# bitbox_rev2b_05_sym.net
KiCad netlist of a schematic drawn in EAGLE
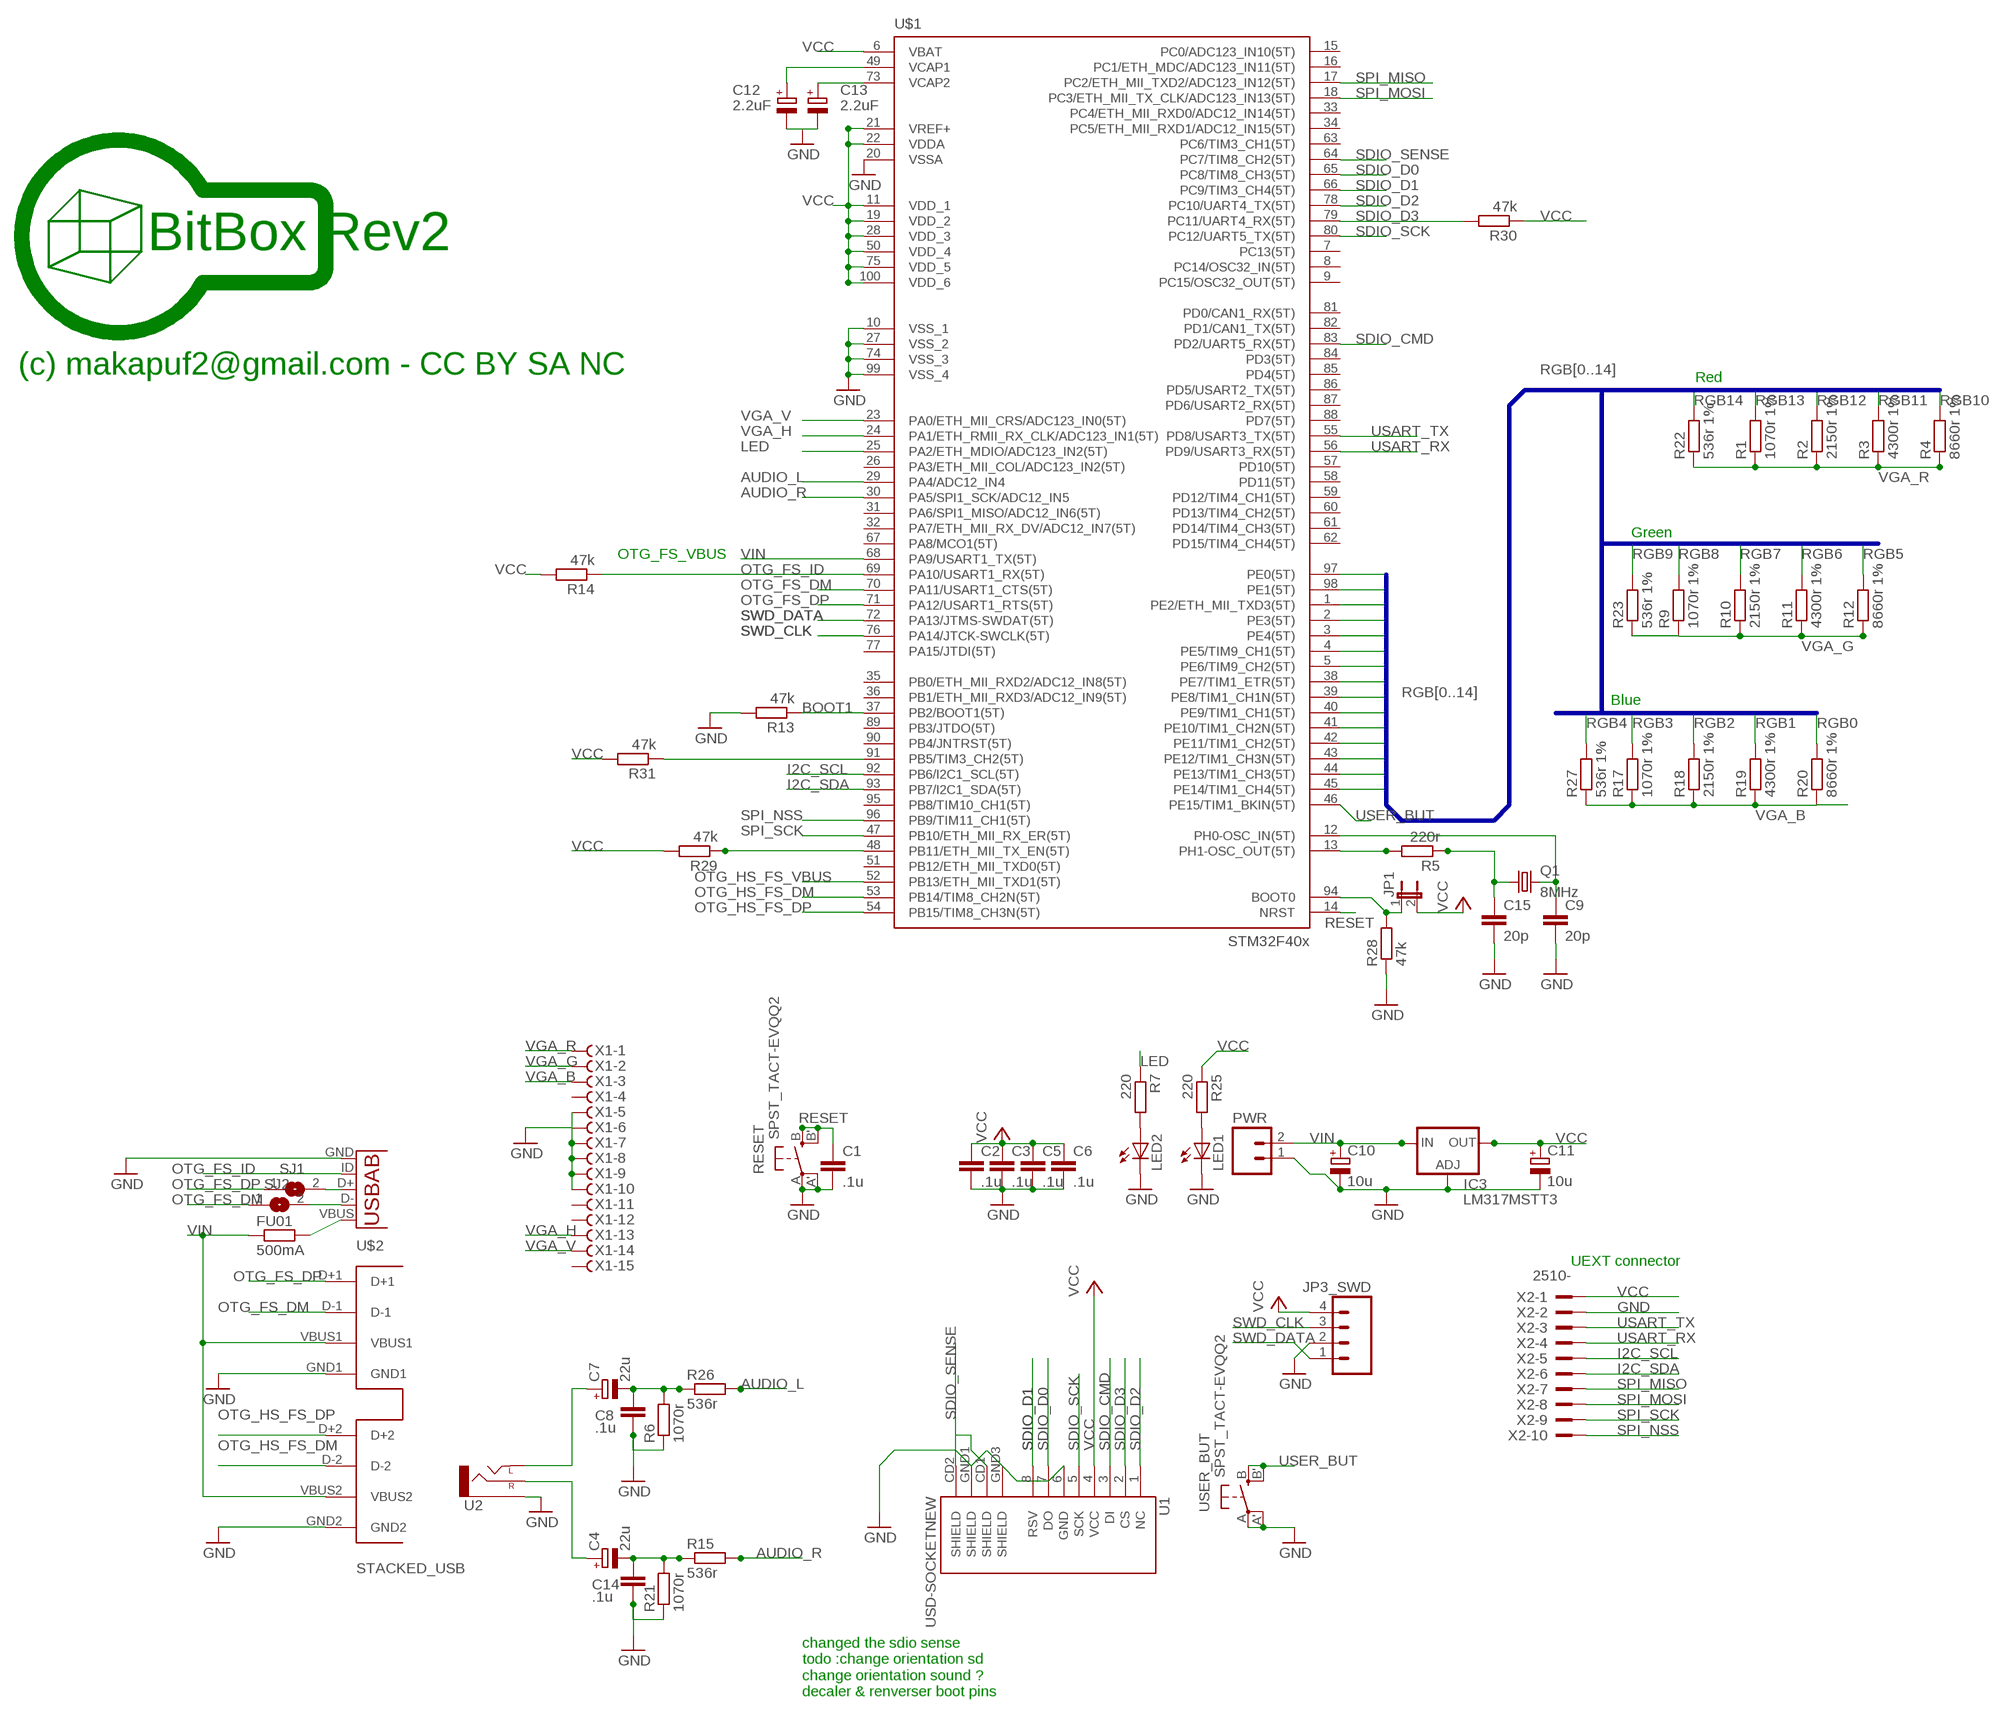
[diagram p0: schematic, sheet 1]

(export (version "E")
  (design (tool "Eeschema 10.0.6"))
  (components
    (comp (ref "C1")
      (value ".1u")
      (footprint "eagle-import:C0603")
      (libsource (lib "eagle-import") (part "C-EUC0603"))
    )
    (comp (ref "C2")
      (value ".1u")
      (footprint "eagle-import:C0603")
      (libsource (lib "eagle-import") (part "C-EUC0603"))
    )
    (comp (ref "C3")
      (value ".1u")
      (footprint "eagle-import:C0603")
      (libsource (lib "eagle-import") (part "C-EUC0603"))
    )
    (comp (ref "C4")
      (value "22u")
      (footprint "eagle-import:153CLV-0505")
      (libsource (lib "eagle-import") (part "CPOL-EU153CLV-0505"))
    )
    (comp (ref "C5")
      (value ".1u")
      (footprint "eagle-import:C0603")
      (libsource (lib "eagle-import") (part "C-EUC0603"))
    )
    (comp (ref "C6")
      (value ".1u")
      (footprint "eagle-import:C0603")
      (libsource (lib "eagle-import") (part "C-EUC0603"))
    )
    (comp (ref "C7")
      (value "22u")
      (footprint "eagle-import:153CLV-0505")
      (libsource (lib "eagle-import") (part "CPOL-EU153CLV-0505"))
    )
    (comp (ref "C8")
      (value ".1u")
      (footprint "eagle-import:C0603")
      (libsource (lib "eagle-import") (part "C-EUC0603"))
    )
    (comp (ref "C9")
      (value "20p")
      (footprint "eagle-import:C0603")
      (libsource (lib "eagle-import") (part "C-EUC0603"))
    )
    (comp (ref "C10")
      (value "10u")
      (footprint "eagle-import:SMC_A")
      (libsource (lib "eagle-import") (part "CPOL-EUSMCA"))
    )
    (comp (ref "C11")
      (value "10u")
      (footprint "eagle-import:SMC_A")
      (libsource (lib "eagle-import") (part "CPOL-EUSMCA"))
    )
    (comp (ref "C12")
      (value "2.2uF")
      (footprint "eagle-import:SMC_A")
      (libsource (lib "eagle-import") (part "CPOL-EUSMCA"))
    )
    (comp (ref "C13")
      (value "2.2uF")
      (footprint "eagle-import:SMC_A")
      (libsource (lib "eagle-import") (part "CPOL-EUSMCA"))
    )
    (comp (ref "C14")
      (value ".1u")
      (footprint "eagle-import:C0603")
      (libsource (lib "eagle-import") (part "C-EUC0603"))
    )
    (comp (ref "C15")
      (value "20p")
      (footprint "eagle-import:C0603")
      (libsource (lib "eagle-import") (part "C-EUC0603"))
    )
    (comp (ref "FU01")
      (value "500mA")
      (footprint "eagle-import:R1206")
      (libsource (lib "eagle-import") (part "R-EU_R1206"))
    )
    (comp (ref "IC3")
      (value "LM317MSTT3")
      (footprint "eagle-import:SOT223")
      (libsource (lib "eagle-import") (part "LM317?MSTT3"))
    )
    (comp (ref "JP1")
      (value "JP1E")
      (footprint "eagle-import:JP1")
      (libsource (lib "eagle-import") (part "JP1E"))
    )
    (comp (ref "JP3_SWD")
      (value "M04PTH")
      (footprint "eagle-import:1X04")
      (libsource (lib "eagle-import") (part "M04PTH"))
    )
    (comp (ref "LED1")
      (value "LEDCHIPLED_0805")
      (footprint "eagle-import:CHIPLED_0805")
      (libsource (lib "eagle-import") (part "LEDCHIPLED_0805"))
    )
    (comp (ref "LED2")
      (value "LEDCHIPLED_0805")
      (footprint "eagle-import:CHIPLED_0805")
      (libsource (lib "eagle-import") (part "LEDCHIPLED_0805"))
    )
    (comp (ref "PWR")
      (value "M02PTH")
      (footprint "eagle-import:1X02")
      (libsource (lib "eagle-import") (part "M02PTH"))
    )
    (comp (ref "Q1")
      (value "8MHz")
      (footprint "eagle-import:SM49")
      (fields (field (name "OC_FARNELL") "unknown"))
      (libsource (lib "eagle-import") (part "CRYSTALSM49"))
    )
    (comp (ref "R1")
      (value "1070r 1%")
      (footprint "eagle-import:R0603")
      (libsource (lib "eagle-import") (part "R-EU_R0603"))
    )
    (comp (ref "R2")
      (value "2150r 1%")
      (footprint "eagle-import:R0603")
      (libsource (lib "eagle-import") (part "R-EU_R0603"))
    )
    (comp (ref "R3")
      (value "4300r 1%")
      (footprint "eagle-import:R0603")
      (libsource (lib "eagle-import") (part "R-EU_R0603"))
    )
    (comp (ref "R4")
      (value "8660r 1%")
      (footprint "eagle-import:R0603")
      (libsource (lib "eagle-import") (part "R-EU_R0603"))
    )
    (comp (ref "R5")
      (value "220r")
      (footprint "eagle-import:R0603")
      (libsource (lib "eagle-import") (part "R-EU_R0603"))
    )
    (comp (ref "R6")
      (value "1070r")
      (footprint "eagle-import:R0603")
      (libsource (lib "eagle-import") (part "R-EU_R0603"))
    )
    (comp (ref "R7")
      (value "220")
      (footprint "eagle-import:R0603")
      (libsource (lib "eagle-import") (part "R-EU_R0603"))
    )
    (comp (ref "R9")
      (value "1070r 1%")
      (footprint "eagle-import:R0603")
      (libsource (lib "eagle-import") (part "R-EU_R0603"))
    )
    (comp (ref "R10")
      (value "2150r 1%")
      (footprint "eagle-import:R0603")
      (libsource (lib "eagle-import") (part "R-EU_R0603"))
    )
    (comp (ref "R11")
      (value "4300r 1%")
      (footprint "eagle-import:R0603")
      (libsource (lib "eagle-import") (part "R-EU_R0603"))
    )
    (comp (ref "R12")
      (value "8660r 1%")
      (footprint "eagle-import:R0603")
      (libsource (lib "eagle-import") (part "R-EU_R0603"))
    )
    (comp (ref "R13")
      (value "47k")
      (footprint "eagle-import:R0603")
      (libsource (lib "eagle-import") (part "R-EU_R0603"))
    )
    (comp (ref "R14")
      (value "47k")
      (footprint "eagle-import:R0603")
      (libsource (lib "eagle-import") (part "R-EU_R0603"))
    )
    (comp (ref "R15")
      (value "536r")
      (footprint "eagle-import:R0603")
      (libsource (lib "eagle-import") (part "R-EU_R0603"))
    )
    (comp (ref "R17")
      (value "1070r 1%")
      (footprint "eagle-import:R0603")
      (libsource (lib "eagle-import") (part "R-EU_R0603"))
    )
    (comp (ref "R18")
      (value "2150r 1%")
      (footprint "eagle-import:R0603")
      (libsource (lib "eagle-import") (part "R-EU_R0603"))
    )
    (comp (ref "R19")
      (value "4300r 1%")
      (footprint "eagle-import:R0603")
      (libsource (lib "eagle-import") (part "R-EU_R0603"))
    )
    (comp (ref "R20")
      (value "8660r 1%")
      (footprint "eagle-import:R0603")
      (libsource (lib "eagle-import") (part "R-EU_R0603"))
    )
    (comp (ref "R21")
      (value "1070r")
      (footprint "eagle-import:R0603")
      (libsource (lib "eagle-import") (part "R-EU_R0603"))
    )
    (comp (ref "R22")
      (value "536r 1%")
      (footprint "eagle-import:R0603")
      (libsource (lib "eagle-import") (part "R-EU_R0603"))
    )
    (comp (ref "R23")
      (value "536r 1%")
      (footprint "eagle-import:R0603")
      (libsource (lib "eagle-import") (part "R-EU_R0603"))
    )
    (comp (ref "R25")
      (value "220")
      (footprint "eagle-import:R0603")
      (libsource (lib "eagle-import") (part "R-EU_R0603"))
    )
    (comp (ref "R26")
      (value "536r")
      (footprint "eagle-import:R0603")
      (libsource (lib "eagle-import") (part "R-EU_R0603"))
    )
    (comp (ref "R27")
      (value "536r 1%")
      (footprint "eagle-import:R0603")
      (libsource (lib "eagle-import") (part "R-EU_R0603"))
    )
    (comp (ref "R28")
      (value "47k")
      (footprint "eagle-import:R0603")
      (libsource (lib "eagle-import") (part "R-EU_R0603"))
    )
    (comp (ref "R29")
      (value "47k")
      (footprint "eagle-import:R0603")
      (libsource (lib "eagle-import") (part "R-EU_R0603"))
    )
    (comp (ref "R30")
      (value "47k")
      (footprint "eagle-import:R0603")
      (libsource (lib "eagle-import") (part "R-EU_R0603"))
    )
    (comp (ref "R31")
      (value "47k")
      (footprint "eagle-import:R0603")
      (libsource (lib "eagle-import") (part "R-EU_R0603"))
    )
    (comp (ref "RESET")
      (value "SPST_TACT-EVQQ2")
      (footprint "eagle-import:EVQ-Q2")
      (libsource (lib "eagle-import") (part "SPST_TACT-EVQQ2"))
    )
    (comp (ref "SJ1") (value "SJ") (footprint "eagle-import:SJ") (libsource (lib "eagle-import") (part "SJ")))
    (comp (ref "SJ2") (value "SJ") (footprint "eagle-import:SJ") (libsource (lib "eagle-import") (part "SJ")))
    (comp (ref "U$1")
      (value "STM32F407V")
      (footprint "eagle-import:TQFP100")
      (libsource (lib "eagle-import") (part "STM32F407V"))
    )
    (comp (ref "U$2")
      (value "STACKED_USB")
      (footprint "eagle-import:2STACKED")
      (libsource (lib "eagle-import") (part "STACKED_USB"))
    )
    (comp (ref "U1")
      (value "USD-SOCKETNEW")
      (footprint "eagle-import:MICRO-SD-SOCKET-PP")
      (libsource (lib "eagle-import") (part "USD-SOCKETNEW"))
    )
    (comp (ref "U2")
      (value "AUDIO-JACKPTH")
      (footprint "eagle-import:AUDIO-JACK")
      (libsource (lib "eagle-import") (part "AUDIO-JACKPTH"))
    )
    (comp (ref "U3")
      (value "USB-AB")
      (footprint "eagle-import:USB-AB-MICRO-SMD")
      (libsource (lib "eagle-import") (part "USB-AB"))
    )
    (comp (ref "USER_BUT")
      (value "SPST_TACT-EVQQ2")
      (footprint "eagle-import:EVQ-Q2")
      (libsource (lib "eagle-import") (part "SPST_TACT-EVQQ2"))
    )
    (comp (ref "X1")
      (value "HF15HS")
      (footprint "eagle-import:HDF15H")
      (libsource (lib "eagle-import") (part "HF15?SH"))
    )
    (comp (ref "X2")
      (value "2510-")
      (footprint "eagle-import:PAK100_2500-10")
      (fields (field (name "MF") "3M") (field (name "MPN") "2510-6002UB"))
      (libsource (lib "eagle-import") (part "2510-"))
    )
  )
  (nets
    (net (code "1") (name "/AUDIO_L") (class "Default")
      (node (ref "R26") (pin "2") (pinfunction "2_2") (pintype "passive"))
      (node (ref "U$1") (pin "29") (pinfunction "PA4/ADC12_IN4_29") (pintype "bidirectional"))
    )
    (net (code "2") (name "/AUDIO_R") (class "Default")
      (node (ref "R15") (pin "2") (pinfunction "2_2") (pintype "passive"))
      (node (ref "U$1") (pin "30") (pinfunction "PA5/SPI1_SCK/ADC12_IN5_30") (pintype "bidirectional"))
    )
    (net (code "3") (name "/BOOT1") (class "Default")
      (node (ref "R13") (pin "1") (pinfunction "1_1") (pintype "passive"))
      (node (ref "U$1") (pin "37") (pinfunction "PB2/BOOT1(5T)_37") (pintype "bidirectional"))
    )
    (net (code "4") (name "/I2C_SCL") (class "Default")
      (node (ref "U$1") (pin "92") (pinfunction "PB6/I2C1_SCL(5T)_92") (pintype "bidirectional"))
      (node (ref "X2") (pin "5") (pinfunction "KL_5") (pintype "passive"))
    )
    (net (code "5") (name "/I2C_SDA") (class "Default")
      (node (ref "U$1") (pin "93") (pinfunction "PB7/I2C1_SDA(5T)_93") (pintype "bidirectional"))
      (node (ref "X2") (pin "6") (pinfunction "KL_6") (pintype "passive"))
    )
    (net (code "6") (name "/LED") (class "Default")
      (node (ref "R7") (pin "1") (pinfunction "1_1") (pintype "passive"))
      (node (ref "U$1") (pin "25") (pinfunction "PA2/ETH_MDIO/ADC123_IN2(5T)_25") (pintype "bidirectional"))
    )
    (net (code "7") (name "/OTG_FS_DM") (class "Default")
      (node (ref "SJ2") (pin "1") (pinfunction "1_1") (pintype "passive"))
      (node (ref "U$1") (pin "70") (pinfunction "PA11/USART1_CTS(5T)_70") (pintype "bidirectional"))
      (node (ref "U$2") (pin "D-1") (pinfunction "D-1_D-1") (pintype "bidirectional"))
    )
    (net (code "8") (name "/OTG_FS_DP") (class "Default")
      (node (ref "SJ1") (pin "1") (pinfunction "1_1") (pintype "passive"))
      (node (ref "U$1") (pin "71") (pinfunction "PA12/USART1_RTS(5T)_71") (pintype "bidirectional"))
      (node (ref "U$2") (pin "D+1") (pinfunction "D+1_D+1") (pintype "bidirectional"))
    )
    (net (code "9") (name "/OTG_FS_ID") (class "Default")
      (node (ref "R14") (pin "1") (pinfunction "1_1") (pintype "passive"))
      (node (ref "U$1") (pin "69") (pinfunction "PA10/USART1_RX(5T)_69") (pintype "bidirectional"))
      (node (ref "U3") (pin "ID") (pinfunction "USBID_ID") (pintype "bidirectional"))
    )
    (net (code "10") (name "/OTG_HS_FS_DM") (class "Default")
      (node (ref "U$1") (pin "53") (pinfunction "PB14/TIM8_CH2N(5T)_53") (pintype "bidirectional"))
      (node (ref "U$2") (pin "D-2") (pinfunction "D-2_D-2") (pintype "bidirectional"))
    )
    (net (code "11") (name "/OTG_HS_FS_DP") (class "Default")
      (node (ref "U$1") (pin "54") (pinfunction "PB15/TIM8_CH3N(5T)_54") (pintype "bidirectional"))
      (node (ref "U$2") (pin "D+2") (pinfunction "D+2_D+2") (pintype "bidirectional"))
    )
    (net (code "12") (name "/OTG_HS_FS_VBUS") (class "Default")
      (node (ref "U$1") (pin "52") (pinfunction "PB13/ETH_MII_TXD1(5T)_52") (pintype "bidirectional"))
    )
    (net (code "13") (name "/RESET") (class "Default")
      (node (ref "C1") (pin "1") (pinfunction "1_1") (pintype "passive"))
      (node (ref "RESET") (pin "B") (pinfunction "S_B") (pintype "passive"))
      (node (ref "RESET") (pin "B'") (pinfunction "S1_B'") (pintype "passive"))
      (node (ref "U$1") (pin "14") (pinfunction "NRST_14") (pintype "bidirectional"))
    )
    (net (code "14") (name "/RGB0") (class "Default")
      (node (ref "R20") (pin "2") (pinfunction "2_2") (pintype "passive"))
      (node (ref "U$1") (pin "97") (pinfunction "PE0(5T)_97") (pintype "bidirectional"))
    )
    (net (code "15") (name "/RGB1") (class "Default")
      (node (ref "R19") (pin "2") (pinfunction "2_2") (pintype "passive"))
      (node (ref "U$1") (pin "98") (pinfunction "PE1(5T)_98") (pintype "bidirectional"))
    )
    (net (code "16") (name "/RGB2") (class "Default")
      (node (ref "R18") (pin "2") (pinfunction "2_2") (pintype "passive"))
      (node (ref "U$1") (pin "1") (pinfunction "PE2/ETH_MII_TXD3(5T)_1") (pintype "bidirectional"))
    )
    (net (code "17") (name "/RGB3") (class "Default")
      (node (ref "R17") (pin "2") (pinfunction "2_2") (pintype "passive"))
      (node (ref "U$1") (pin "2") (pinfunction "PE3(5T)_2") (pintype "bidirectional"))
    )
    (net (code "18") (name "/RGB4") (class "Default")
      (node (ref "R27") (pin "2") (pinfunction "2_2") (pintype "passive"))
      (node (ref "U$1") (pin "3") (pinfunction "PE4(5T)_3") (pintype "bidirectional"))
    )
    (net (code "19") (name "/RGB5") (class "Default")
      (node (ref "R12") (pin "2") (pinfunction "2_2") (pintype "passive"))
      (node (ref "U$1") (pin "4") (pinfunction "PE5/TIM9_CH1(5T)_4") (pintype "bidirectional"))
    )
    (net (code "20") (name "/RGB6") (class "Default")
      (node (ref "R11") (pin "2") (pinfunction "2_2") (pintype "passive"))
      (node (ref "U$1") (pin "5") (pinfunction "PE6/TIM9_CH2(5T)_5") (pintype "bidirectional"))
    )
    (net (code "21") (name "/RGB7") (class "Default")
      (node (ref "R10") (pin "2") (pinfunction "2_2") (pintype "passive"))
      (node (ref "U$1") (pin "38") (pinfunction "PE7/TIM1_ETR(5T)_38") (pintype "bidirectional"))
    )
    (net (code "22") (name "/RGB8") (class "Default")
      (node (ref "R9") (pin "2") (pinfunction "2_2") (pintype "passive"))
      (node (ref "U$1") (pin "39") (pinfunction "PE8/TIM1_CH1N(5T)_39") (pintype "bidirectional"))
    )
    (net (code "23") (name "/RGB9") (class "Default")
      (node (ref "R23") (pin "2") (pinfunction "2_2") (pintype "passive"))
      (node (ref "U$1") (pin "40") (pinfunction "PE9/TIM1_CH1(5T)_40") (pintype "bidirectional"))
    )
    (net (code "24") (name "/RGB10") (class "Default")
      (node (ref "R4") (pin "2") (pinfunction "2_2") (pintype "passive"))
      (node (ref "U$1") (pin "41") (pinfunction "PE10/TIM1_CH2N(5T)_41") (pintype "bidirectional"))
    )
    (net (code "25") (name "/RGB11") (class "Default")
      (node (ref "R3") (pin "2") (pinfunction "2_2") (pintype "passive"))
      (node (ref "U$1") (pin "42") (pinfunction "PE11/TIM1_CH2(5T)_42") (pintype "bidirectional"))
    )
    (net (code "26") (name "/RGB12") (class "Default")
      (node (ref "R2") (pin "2") (pinfunction "2_2") (pintype "passive"))
      (node (ref "U$1") (pin "43") (pinfunction "PE12/TIM1_CH3N(5T)_43") (pintype "bidirectional"))
    )
    (net (code "27") (name "/RGB13") (class "Default")
      (node (ref "R1") (pin "2") (pinfunction "2_2") (pintype "passive"))
      (node (ref "U$1") (pin "44") (pinfunction "PE13/TIM1_CH3(5T)_44") (pintype "bidirectional"))
    )
    (net (code "28") (name "/RGB14") (class "Default")
      (node (ref "R22") (pin "2") (pinfunction "2_2") (pintype "passive"))
      (node (ref "U$1") (pin "45") (pinfunction "PE14/TIM1_CH4(5T)_45") (pintype "bidirectional"))
    )
    (net (code "30") (name "/SDIO_CMD") (class "Default")
      (node (ref "U$1") (pin "83") (pinfunction "PD2/UART5_RX(5T)_83") (pintype "bidirectional"))
      (node (ref "U1") (pin "3") (pinfunction "DI_3") (pintype "bidirectional"))
    )
    (net (code "31") (name "/SDIO_D0") (class "Default")
      (node (ref "U$1") (pin "65") (pinfunction "PC8/TIM8_CH3(5T)_65") (pintype "bidirectional"))
      (node (ref "U1") (pin "7") (pinfunction "DO_7") (pintype "bidirectional"))
    )
    (net (code "32") (name "/SDIO_D1") (class "Default")
      (node (ref "U$1") (pin "66") (pinfunction "PC9/TIM3_CH4(5T)_66") (pintype "bidirectional"))
      (node (ref "U1") (pin "8") (pinfunction "RSV_8") (pintype "bidirectional"))
    )
    (net (code "33") (name "/SDIO_D2") (class "Default")
      (node (ref "U$1") (pin "78") (pinfunction "PC10/UART4_TX(5T)_78") (pintype "bidirectional"))
      (node (ref "U1") (pin "1") (pinfunction "NC_1") (pintype "bidirectional"))
    )
    (net (code "34") (name "/SDIO_D3") (class "Default")
      (node (ref "R30") (pin "2") (pinfunction "2_2") (pintype "passive"))
      (node (ref "U$1") (pin "79") (pinfunction "PC11/UART4_RX(5T)_79") (pintype "bidirectional"))
      (node (ref "U1") (pin "2") (pinfunction "CS_2") (pintype "bidirectional"))
    )
    (net (code "35") (name "/SDIO_SCK") (class "Default")
      (node (ref "U$1") (pin "80") (pinfunction "PC12/UART5_TX(5T)_80") (pintype "bidirectional"))
      (node (ref "U1") (pin "5") (pinfunction "SCK_5") (pintype "bidirectional"))
    )
    (net (code "36") (name "/SDIO_SENSE") (class "Default")
      (node (ref "U$1") (pin "64") (pinfunction "PC7/TIM8_CH2(5T)_64") (pintype "bidirectional"))
      (node (ref "U1") (pin "CD1") (pinfunction "SHIELD_CD1") (pintype "bidirectional"))
      (node (ref "U1") (pin "CD2") (pinfunction "SHIELD_CD2") (pintype "bidirectional"))
    )
    (net (code "37") (name "/SPI_MISO") (class "Default")
      (node (ref "U$1") (pin "17") (pinfunction "PC2/ETH_MII_TXD2/ADC123_IN12(5T)_17") (pintype "bidirectional"))
      (node (ref "X2") (pin "7") (pinfunction "KL_7") (pintype "passive"))
    )
    (net (code "38") (name "/SPI_MOSI") (class "Default")
      (node (ref "U$1") (pin "18") (pinfunction "PC3/ETH_MII_TX_CLK/ADC123_IN13(5T)_18") (pintype "bidirectional"))
      (node (ref "X2") (pin "8") (pinfunction "KL_8") (pintype "passive"))
    )
    (net (code "39") (name "/SPI_NSS") (class "Default")
      (node (ref "U$1") (pin "96") (pinfunction "PB9/TIM11_CH1(5T)_96") (pintype "bidirectional"))
      (node (ref "X2") (pin "10") (pinfunction "KL_10") (pintype "passive"))
    )
    (net (code "40") (name "/SPI_SCK") (class "Default")
      (node (ref "U$1") (pin "47") (pinfunction "PB10/ETH_MII_RX_ER(5T)_47") (pintype "bidirectional"))
      (node (ref "X2") (pin "9") (pinfunction "KL_9") (pintype "passive"))
    )
    (net (code "41") (name "/SWD_CLK") (class "Default")
      (node (ref "JP3_SWD") (pin "3") (pinfunction "3_3") (pintype "passive"))
      (node (ref "U$1") (pin "76") (pinfunction "PA14/JTCK-SWCLK(5T)_76") (pintype "bidirectional"))
    )
    (net (code "42") (name "/SWD_DATA") (class "Default")
      (node (ref "JP3_SWD") (pin "1") (pinfunction "1_1") (pintype "passive"))
      (node (ref "U$1") (pin "72") (pinfunction "PA13/JTMS-SWDAT(5T)_72") (pintype "bidirectional"))
    )
    (net (code "43") (name "/USART_RX") (class "Default")
      (node (ref "U$1") (pin "56") (pinfunction "PD9/USART3_RX(5T)_56") (pintype "bidirectional"))
      (node (ref "X2") (pin "4") (pinfunction "KL_4") (pintype "passive"))
    )
    (net (code "44") (name "/USART_TX") (class "Default")
      (node (ref "U$1") (pin "55") (pinfunction "PD8/USART3_TX(5T)_55") (pintype "bidirectional"))
      (node (ref "X2") (pin "3") (pinfunction "KL_3") (pintype "passive"))
    )
    (net (code "45") (name "/USER_BUT") (class "Default")
      (node (ref "U$1") (pin "46") (pinfunction "PE15/TIM1_BKIN(5T)_46") (pintype "bidirectional"))
      (node (ref "USER_BUT") (pin "B") (pinfunction "S_B") (pintype "passive"))
      (node (ref "USER_BUT") (pin "B'") (pinfunction "S1_B'") (pintype "passive"))
    )
    (net (code "46") (name "/VGA_B") (class "Default")
      (node (ref "R17") (pin "1") (pinfunction "1_1") (pintype "passive"))
      (node (ref "R18") (pin "1") (pinfunction "1_1") (pintype "passive"))
      (node (ref "R19") (pin "1") (pinfunction "1_1") (pintype "passive"))
      (node (ref "R20") (pin "1") (pinfunction "1_1") (pintype "passive"))
      (node (ref "R27") (pin "1") (pinfunction "1_1") (pintype "passive"))
      (node (ref "X1") (pin "3") (pinfunction "F_3") (pintype "passive"))
    )
    (net (code "47") (name "/VGA_G") (class "Default")
      (node (ref "R10") (pin "1") (pinfunction "1_1") (pintype "passive"))
      (node (ref "R11") (pin "1") (pinfunction "1_1") (pintype "passive"))
      (node (ref "R12") (pin "1") (pinfunction "1_1") (pintype "passive"))
      (node (ref "R23") (pin "1") (pinfunction "1_1") (pintype "passive"))
      (node (ref "R9") (pin "1") (pinfunction "1_1") (pintype "passive"))
      (node (ref "X1") (pin "2") (pinfunction "F_2") (pintype "passive"))
    )
    (net (code "48") (name "/VGA_H") (class "Default")
      (node (ref "U$1") (pin "24") (pinfunction "PA1/ETH_RMII_RX_CLK/ADC123_IN1(5T)_24") (pintype "bidirectional"))
      (node (ref "X1") (pin "13") (pinfunction "F_13") (pintype "passive"))
    )
    (net (code "49") (name "/VGA_R") (class "Default")
      (node (ref "R1") (pin "1") (pinfunction "1_1") (pintype "passive"))
      (node (ref "R2") (pin "1") (pinfunction "1_1") (pintype "passive"))
      (node (ref "R22") (pin "1") (pinfunction "1_1") (pintype "passive"))
      (node (ref "R3") (pin "1") (pinfunction "1_1") (pintype "passive"))
      (node (ref "R4") (pin "1") (pinfunction "1_1") (pintype "passive"))
      (node (ref "X1") (pin "1") (pinfunction "F_1") (pintype "passive"))
    )
    (net (code "50") (name "/VGA_V") (class "Default")
      (node (ref "U$1") (pin "23") (pinfunction "PA0/ETH_MII_CRS/ADC123_IN0(5T)_23") (pintype "bidirectional"))
      (node (ref "X1") (pin "14") (pinfunction "F_14") (pintype "passive"))
    )
    (net (code "51") (name "/VIN") (class "Default")
      (node (ref "C10") (pin "+") (pinfunction "+_+") (pintype "passive"))
      (node (ref "FU01") (pin "1") (pinfunction "1_1") (pintype "passive"))
      (node (ref "IC3") (pin "3") (pinfunction "IN_3") (pintype "input"))
      (node (ref "PWR") (pin "2") (pinfunction "2_2") (pintype "passive"))
      (node (ref "U$1") (pin "68") (pinfunction "PA9/USART1_TX(5T)_68") (pintype "bidirectional"))
      (node (ref "U$2") (pin "VBUS1") (pinfunction "VBUS1_VBUS1") (pintype "bidirectional"))
      (node (ref "U$2") (pin "VBUS2") (pinfunction "VBUS2_VBUS2") (pintype "bidirectional"))
    )
    (net (code "52") (name "GND") (class "Default")
      (node (ref "C1") (pin "2") (pinfunction "2_2") (pintype "passive"))
      (node (ref "C10") (pin "-") (pinfunction "-_-") (pintype "passive"))
      (node (ref "C11") (pin "-") (pinfunction "-_-") (pintype "passive"))
      (node (ref "C12") (pin "-") (pinfunction "-_-") (pintype "passive"))
      (node (ref "C13") (pin "-") (pinfunction "-_-") (pintype "passive"))
      (node (ref "C14") (pin "2") (pinfunction "2_2") (pintype "passive"))
      (node (ref "C15") (pin "2") (pinfunction "2_2") (pintype "passive"))
      (node (ref "C2") (pin "2") (pinfunction "2_2") (pintype "passive"))
      (node (ref "C3") (pin "2") (pinfunction "2_2") (pintype "passive"))
      (node (ref "C5") (pin "2") (pinfunction "2_2") (pintype "passive"))
      (node (ref "C6") (pin "2") (pinfunction "2_2") (pintype "passive"))
      (node (ref "C8") (pin "2") (pinfunction "2_2") (pintype "passive"))
      (node (ref "C9") (pin "2") (pinfunction "2_2") (pintype "passive"))
      (node (ref "IC3") (pin "1") (pinfunction "ADJ_1") (pintype "input"))
      (node (ref "JP3_SWD") (pin "2") (pinfunction "2_2") (pintype "passive"))
      (node (ref "LED1") (pin "C") (pinfunction "C_C") (pintype "passive"))
      (node (ref "LED2") (pin "C") (pinfunction "C_C") (pintype "passive"))
      (node (ref "PWR") (pin "1") (pinfunction "1_1") (pintype "passive"))
      (node (ref "R13") (pin "2") (pinfunction "2_2") (pintype "passive"))
      (node (ref "R21") (pin "1") (pinfunction "1_1") (pintype "passive"))
      (node (ref "R28") (pin "1") (pinfunction "1_1") (pintype "passive"))
      (node (ref "R6") (pin "1") (pinfunction "1_1") (pintype "passive"))
      (node (ref "RESET") (pin "A") (pinfunction "P_A") (pintype "passive"))
      (node (ref "RESET") (pin "A'") (pinfunction "P1_A'") (pintype "passive"))
      (node (ref "U$1") (pin "10") (pinfunction "VSS_1_10") (pintype "bidirectional"))
      (node (ref "U$1") (pin "20") (pinfunction "VSSA_20") (pintype "bidirectional"))
      (node (ref "U$1") (pin "27") (pinfunction "VSS_2_27") (pintype "bidirectional"))
      (node (ref "U$1") (pin "74") (pinfunction "VSS_3_74") (pintype "bidirectional"))
      (node (ref "U$1") (pin "99") (pinfunction "VSS_4_99") (pintype "bidirectional"))
      (node (ref "U$2") (pin "GND1") (pinfunction "GND1_GND1") (pintype "bidirectional"))
      (node (ref "U$2") (pin "GND2") (pinfunction "GND2_GND2") (pintype "bidirectional"))
      (node (ref "U1") (pin "6") (pinfunction "GND_6") (pintype "bidirectional"))
      (node (ref "U1") (pin "GND1") (pinfunction "SHIELD_GND1") (pintype "bidirectional"))
      (node (ref "U1") (pin "GND3") (pinfunction "SHIELD_GND3") (pintype "bidirectional"))
      (node (ref "U2") (pin "SLEEVE") (pinfunction "SLEEVE_SLEEVE") (pintype "bidirectional"))
      (node (ref "U3") (pin "GND") (pinfunction "GND_GND") (pintype "bidirectional"))
      (node (ref "USER_BUT") (pin "A") (pinfunction "P_A") (pintype "passive"))
      (node (ref "USER_BUT") (pin "A'") (pinfunction "P1_A'") (pintype "passive"))
      (node (ref "X1") (pin "10") (pinfunction "F_10") (pintype "passive"))
      (node (ref "X1") (pin "5") (pinfunction "F_5") (pintype "passive"))
      (node (ref "X1") (pin "6") (pinfunction "F_6") (pintype "passive"))
      (node (ref "X1") (pin "7") (pinfunction "F_7") (pintype "passive"))
      (node (ref "X1") (pin "8") (pinfunction "F_8") (pintype "passive"))
      (node (ref "X1") (pin "9") (pinfunction "F_9") (pintype "passive"))
      (node (ref "X2") (pin "2") (pinfunction "KL_2") (pintype "passive"))
    )
    (net (code "53") (name "Net-(C7-Pad-)") (class "Default")
      (node (ref "C7") (pin "-") (pinfunction "-_-") (pintype "passive"))
      (node (ref "C8") (pin "1") (pinfunction "1_1") (pintype "passive"))
      (node (ref "R26") (pin "1") (pinfunction "1_1") (pintype "passive"))
      (node (ref "R6") (pin "2") (pinfunction "2_2") (pintype "passive"))
    )
    (net (code "54") (name "Net-(C14-Pad1)") (class "Default")
      (node (ref "C14") (pin "1") (pinfunction "1_1") (pintype "passive"))
      (node (ref "C4") (pin "-") (pinfunction "-_-") (pintype "passive"))
      (node (ref "R15") (pin "1") (pinfunction "1_1") (pintype "passive"))
      (node (ref "R21") (pin "2") (pinfunction "2_2") (pintype "passive"))
    )
    (net (code "55") (name "Net-(C15-Pad1)") (class "Default")
      (node (ref "C15") (pin "1") (pinfunction "1_1") (pintype "passive"))
      (node (ref "Q1") (pin "1") (pinfunction "1_1") (pintype "passive"))
      (node (ref "R5") (pin "1") (pinfunction "1_1") (pintype "passive"))
    )
    (net (code "56") (name "Net-(FU01-Pad2)") (class "Default")
      (node (ref "FU01") (pin "2") (pinfunction "2_2") (pintype "passive"))
      (node (ref "U3") (pin "VBUS") (pinfunction "VBUS_VBUS") (pintype "bidirectional"))
    )
    (net (code "57") (name "Net-(LED1-PadA)") (class "Default")
      (node (ref "LED1") (pin "A") (pinfunction "A_A") (pintype "passive"))
      (node (ref "R25") (pin "2") (pinfunction "2_2") (pintype "passive"))
    )
    (net (code "58") (name "Net-(LED2-PadA)") (class "Default")
      (node (ref "LED2") (pin "A") (pinfunction "A_A") (pintype "passive"))
      (node (ref "R7") (pin "2") (pinfunction "2_2") (pintype "passive"))
    )
    (net (code "59") (name "Net-(SJ1-Pad2)") (class "Default")
      (node (ref "SJ1") (pin "2") (pinfunction "2_2") (pintype "passive"))
      (node (ref "U3") (pin "D+") (pinfunction "D+_D+") (pintype "bidirectional"))
    )
    (net (code "60") (name "Net-(SJ2-Pad2)") (class "Default")
      (node (ref "SJ2") (pin "2") (pinfunction "2_2") (pintype "passive"))
      (node (ref "U3") (pin "D-") (pinfunction "D-_D-") (pintype "bidirectional"))
    )
    (net (code "61") (name "Net-(U$1-BOOT0)") (class "Default")
      (node (ref "JP1") (pin "1") (pinfunction "1_1") (pintype "passive"))
      (node (ref "R28") (pin "2") (pinfunction "2_2") (pintype "passive"))
      (node (ref "U$1") (pin "94") (pinfunction "BOOT0_94") (pintype "bidirectional"))
    )
    (net (code "62") (name "Net-(U$1-PB5{slash}TIM3_CH2(5T))") (class "Default")
      (node (ref "R31") (pin "1") (pinfunction "1_1") (pintype "passive"))
      (node (ref "U$1") (pin "91") (pinfunction "PB5/TIM3_CH2(5T)_91") (pintype "bidirectional"))
    )
    (net (code "63") (name "Net-(U$1-PB11{slash}ETH_MII_TX_EN(5T))") (class "Default")
      (node (ref "R29") (pin "1") (pinfunction "1_1") (pintype "passive"))
      (node (ref "U$1") (pin "48") (pinfunction "PB11/ETH_MII_TX_EN(5T)_48") (pintype "bidirectional"))
    )
    (net (code "64") (name "Net-(U$1-PH0-OSC_IN(5T))") (class "Default")
      (node (ref "C9") (pin "1") (pinfunction "1_1") (pintype "passive"))
      (node (ref "Q1") (pin "2") (pinfunction "2_2") (pintype "passive"))
      (node (ref "U$1") (pin "12") (pinfunction "PH0-OSC_IN(5T)_12") (pintype "bidirectional"))
    )
    (net (code "65") (name "Net-(U$1-PH1-OSC_OUT(5T))") (class "Default")
      (node (ref "R5") (pin "2") (pinfunction "2_2") (pintype "passive"))
      (node (ref "U$1") (pin "13") (pinfunction "PH1-OSC_OUT(5T)_13") (pintype "bidirectional"))
    )
    (net (code "66") (name "Net-(U$1-VCAP1)") (class "Default")
      (node (ref "C12") (pin "+") (pinfunction "+_+") (pintype "passive"))
      (node (ref "U$1") (pin "49") (pinfunction "VCAP1_49") (pintype "bidirectional"))
    )
    (net (code "67") (name "Net-(U$1-VCAP2)") (class "Default")
      (node (ref "C13") (pin "+") (pinfunction "+_+") (pintype "passive"))
      (node (ref "U$1") (pin "73") (pinfunction "VCAP2_73") (pintype "bidirectional"))
    )
    (net (code "68") (name "Net-(U2-LEFT)") (class "Default")
      (node (ref "C7") (pin "+") (pinfunction "+_+") (pintype "passive"))
      (node (ref "U2") (pin "TIP") (pinfunction "LEFT_TIP") (pintype "bidirectional"))
    )
    (net (code "69") (name "Net-(U2-RIGHT)") (class "Default")
      (node (ref "C4") (pin "+") (pinfunction "+_+") (pintype "passive"))
      (node (ref "U2") (pin "RING") (pinfunction "RIGHT_RING") (pintype "bidirectional"))
    )
    (net (code "70") (name "VCC") (class "Default")
      (node (ref "C11") (pin "+") (pinfunction "+_+") (pintype "passive"))
      (node (ref "C2") (pin "1") (pinfunction "1_1") (pintype "passive"))
      (node (ref "C3") (pin "1") (pinfunction "1_1") (pintype "passive"))
      (node (ref "C5") (pin "1") (pinfunction "1_1") (pintype "passive"))
      (node (ref "C6") (pin "1") (pinfunction "1_1") (pintype "passive"))
      (node (ref "IC3") (pin "4") (pinfunction "OUT_4") (pintype "passive"))
      (node (ref "JP1") (pin "2") (pinfunction "2_2") (pintype "passive"))
      (node (ref "JP3_SWD") (pin "4") (pinfunction "4_4") (pintype "passive"))
      (node (ref "R14") (pin "2") (pinfunction "2_2") (pintype "passive"))
      (node (ref "R25") (pin "1") (pinfunction "1_1") (pintype "passive"))
      (node (ref "R29") (pin "2") (pinfunction "2_2") (pintype "passive"))
      (node (ref "R30") (pin "1") (pinfunction "1_1") (pintype "passive"))
      (node (ref "R31") (pin "2") (pinfunction "2_2") (pintype "passive"))
      (node (ref "U$1") (pin "100") (pinfunction "VDD_6_100") (pintype "bidirectional"))
      (node (ref "U$1") (pin "11") (pinfunction "VDD_1_11") (pintype "bidirectional"))
      (node (ref "U$1") (pin "19") (pinfunction "VDD_2_19") (pintype "bidirectional"))
      (node (ref "U$1") (pin "21") (pinfunction "VREF+_21") (pintype "bidirectional"))
      (node (ref "U$1") (pin "22") (pinfunction "VDDA_22") (pintype "bidirectional"))
      (node (ref "U$1") (pin "28") (pinfunction "VDD_3_28") (pintype "bidirectional"))
      (node (ref "U$1") (pin "50") (pinfunction "VDD_4_50") (pintype "bidirectional"))
      (node (ref "U$1") (pin "6") (pinfunction "VBAT_6") (pintype "bidirectional"))
      (node (ref "U$1") (pin "75") (pinfunction "VDD_5_75") (pintype "bidirectional"))
      (node (ref "U1") (pin "4") (pinfunction "VCC_4") (pintype "bidirectional"))
      (node (ref "X2") (pin "1") (pinfunction "KL_1") (pintype "passive"))
    )
    (net (code "71") (name "unconnected-(U$1-PA3{slash}ETH_MII_COL{slash}ADC123_IN2(5T)-Pad26)") (class "Default")
      (node (ref "U$1") (pin "26") (pinfunction "PA3/ETH_MII_COL/ADC123_IN2(5T)_26") (pintype "bidirectional"))
    )
    (net (code "72") (name "unconnected-(U$1-PA6{slash}SPI1_MISO{slash}ADC12_IN6(5T)-Pad31)") (class "Default")
      (node (ref "U$1") (pin "31") (pinfunction "PA6/SPI1_MISO/ADC12_IN6(5T)_31") (pintype "bidirectional"))
    )
    (net (code "73") (name "unconnected-(U$1-PA7{slash}ETH_MII_RX_DV{slash}ADC12_IN7(5T)-Pad32)") (class "Default")
      (node (ref "U$1") (pin "32") (pinfunction "PA7/ETH_MII_RX_DV/ADC12_IN7(5T)_32") (pintype "bidirectional"))
    )
    (net (code "74") (name "unconnected-(U$1-PA8{slash}MCO1(5T)-Pad67)") (class "Default")
      (node (ref "U$1") (pin "67") (pinfunction "PA8/MCO1(5T)_67") (pintype "bidirectional"))
    )
    (net (code "75") (name "unconnected-(U$1-PA15{slash}JTDI(5T)-Pad77)") (class "Default")
      (node (ref "U$1") (pin "77") (pinfunction "PA15/JTDI(5T)_77") (pintype "bidirectional"))
    )
    (net (code "76") (name "unconnected-(U$1-PB0{slash}ETH_MII_RXD2{slash}ADC12_IN8(5T)-Pad35)") (class "Default")
      (node (ref "U$1") (pin "35") (pinfunction "PB0/ETH_MII_RXD2/ADC12_IN8(5T)_35") (pintype "bidirectional"))
    )
    (net (code "77") (name "unconnected-(U$1-PB1{slash}ETH_MII_RXD3{slash}ADC12_IN9(5T)-Pad36)") (class "Default")
      (node (ref "U$1") (pin "36") (pinfunction "PB1/ETH_MII_RXD3/ADC12_IN9(5T)_36") (pintype "bidirectional"))
    )
    (net (code "78") (name "unconnected-(U$1-PB3{slash}JTDO(5T)-Pad89)") (class "Default")
      (node (ref "U$1") (pin "89") (pinfunction "PB3/JTDO(5T)_89") (pintype "bidirectional"))
    )
    (net (code "79") (name "unconnected-(U$1-PB4{slash}JNTRST(5T)-Pad90)") (class "Default")
      (node (ref "U$1") (pin "90") (pinfunction "PB4/JNTRST(5T)_90") (pintype "bidirectional"))
    )
    (net (code "80") (name "unconnected-(U$1-PB8{slash}TIM10_CH1(5T)-Pad95)") (class "Default")
      (node (ref "U$1") (pin "95") (pinfunction "PB8/TIM10_CH1(5T)_95") (pintype "bidirectional"))
    )
    (net (code "81") (name "unconnected-(U$1-PB12{slash}ETH_MII_TXD0(5T)-Pad51)") (class "Default")
      (node (ref "U$1") (pin "51") (pinfunction "PB12/ETH_MII_TXD0(5T)_51") (pintype "bidirectional"))
    )
    (net (code "82") (name "unconnected-(U$1-PC0{slash}ADC123_IN10(5T)-Pad15)") (class "Default")
      (node (ref "U$1") (pin "15") (pinfunction "PC0/ADC123_IN10(5T)_15") (pintype "bidirectional"))
    )
    (net (code "83") (name "unconnected-(U$1-PC1{slash}ETH_MDC{slash}ADC123_IN11(5T)-Pad16)") (class "Default")
      (node (ref "U$1") (pin "16") (pinfunction "PC1/ETH_MDC/ADC123_IN11(5T)_16") (pintype "bidirectional"))
    )
    (net (code "84") (name "unconnected-(U$1-PC4{slash}ETH_MII_RXD0{slash}ADC12_IN14(5T)-Pad33)") (class "Default")
      (node (ref "U$1") (pin "33") (pinfunction "PC4/ETH_MII_RXD0/ADC12_IN14(5T)_33") (pintype "bidirectional"))
    )
    (net (code "85") (name "unconnected-(U$1-PC5{slash}ETH_MII_RXD1{slash}ADC12_IN15(5T)-Pad34)") (class "Default")
      (node (ref "U$1") (pin "34") (pinfunction "PC5/ETH_MII_RXD1/ADC12_IN15(5T)_34") (pintype "bidirectional"))
    )
    (net (code "86") (name "unconnected-(U$1-PC6{slash}TIM3_CH1(5T)-Pad63)") (class "Default")
      (node (ref "U$1") (pin "63") (pinfunction "PC6/TIM3_CH1(5T)_63") (pintype "bidirectional"))
    )
    (net (code "87") (name "unconnected-(U$1-PC13(5T)-Pad7)") (class "Default")
      (node (ref "U$1") (pin "7") (pinfunction "PC13(5T)_7") (pintype "bidirectional"))
    )
    (net (code "88") (name "unconnected-(U$1-PC14{slash}OSC32_IN(5T)-Pad8)") (class "Default")
      (node (ref "U$1") (pin "8") (pinfunction "PC14/OSC32_IN(5T)_8") (pintype "bidirectional"))
    )
    (net (code "89") (name "unconnected-(U$1-PC15{slash}OSC32_OUT(5T)-Pad9)") (class "Default")
      (node (ref "U$1") (pin "9") (pinfunction "PC15/OSC32_OUT(5T)_9") (pintype "bidirectional"))
    )
    (net (code "90") (name "unconnected-(U$1-PD0{slash}CAN1_RX(5T)-Pad81)") (class "Default")
      (node (ref "U$1") (pin "81") (pinfunction "PD0/CAN1_RX(5T)_81") (pintype "bidirectional"))
    )
    (net (code "91") (name "unconnected-(U$1-PD1{slash}CAN1_TX(5T)-Pad82)") (class "Default")
      (node (ref "U$1") (pin "82") (pinfunction "PD1/CAN1_TX(5T)_82") (pintype "bidirectional"))
    )
    (net (code "92") (name "unconnected-(U$1-PD3(5T)-Pad84)") (class "Default")
      (node (ref "U$1") (pin "84") (pinfunction "PD3(5T)_84") (pintype "bidirectional"))
    )
    (net (code "93") (name "unconnected-(U$1-PD4(5T)-Pad85)") (class "Default")
      (node (ref "U$1") (pin "85") (pinfunction "PD4(5T)_85") (pintype "bidirectional"))
    )
    (net (code "94") (name "unconnected-(U$1-PD5{slash}USART2_TX(5T)-Pad86)") (class "Default")
      (node (ref "U$1") (pin "86") (pinfunction "PD5/USART2_TX(5T)_86") (pintype "bidirectional"))
    )
    (net (code "95") (name "unconnected-(U$1-PD6{slash}USART2_RX(5T)-Pad87)") (class "Default")
      (node (ref "U$1") (pin "87") (pinfunction "PD6/USART2_RX(5T)_87") (pintype "bidirectional"))
    )
    (net (code "96") (name "unconnected-(U$1-PD7(5T)-Pad88)") (class "Default")
      (node (ref "U$1") (pin "88") (pinfunction "PD7(5T)_88") (pintype "bidirectional"))
    )
    (net (code "97") (name "unconnected-(U$1-PD10(5T)-Pad57)") (class "Default")
      (node (ref "U$1") (pin "57") (pinfunction "PD10(5T)_57") (pintype "bidirectional"))
    )
    (net (code "98") (name "unconnected-(U$1-PD11(5T)-Pad58)") (class "Default")
      (node (ref "U$1") (pin "58") (pinfunction "PD11(5T)_58") (pintype "bidirectional"))
    )
    (net (code "99") (name "unconnected-(U$1-PD12{slash}TIM4_CH1(5T)-Pad59)") (class "Default")
      (node (ref "U$1") (pin "59") (pinfunction "PD12/TIM4_CH1(5T)_59") (pintype "bidirectional"))
    )
    (net (code "100") (name "unconnected-(U$1-PD13{slash}TIM4_CH2(5T)-Pad60)") (class "Default")
      (node (ref "U$1") (pin "60") (pinfunction "PD13/TIM4_CH2(5T)_60") (pintype "bidirectional"))
    )
    (net (code "101") (name "unconnected-(U$1-PD14{slash}TIM4_CH3(5T)-Pad61)") (class "Default")
      (node (ref "U$1") (pin "61") (pinfunction "PD14/TIM4_CH3(5T)_61") (pintype "bidirectional"))
    )
    (net (code "102") (name "unconnected-(U$1-PD15{slash}TIM4_CH4(5T)-Pad62)") (class "Default")
      (node (ref "U$1") (pin "62") (pinfunction "PD15/TIM4_CH4(5T)_62") (pintype "bidirectional"))
    )
    (net (code "103") (name "unconnected-(X1C-F-Pad11)") (class "Default")
      (node (ref "X1") (pin "11") (pinfunction "F_11") (pintype "passive"))
    )
    (net (code "104") (name "unconnected-(X1D-F-Pad12)") (class "Default")
      (node (ref "X1") (pin "12") (pinfunction "F_12") (pintype "passive"))
    )
    (net (code "105") (name "unconnected-(X1G-F-Pad15)") (class "Default")
      (node (ref "X1") (pin "15") (pinfunction "F_15") (pintype "passive"))
    )
    (net (code "106") (name "unconnected-(X1J-F-Pad4)") (class "Default")
      (node (ref "X1") (pin "4") (pinfunction "F_4") (pintype "passive"))
    )
  )
)
